# conn.net
KiCad netlist of a schematic drawn in Altium Designer
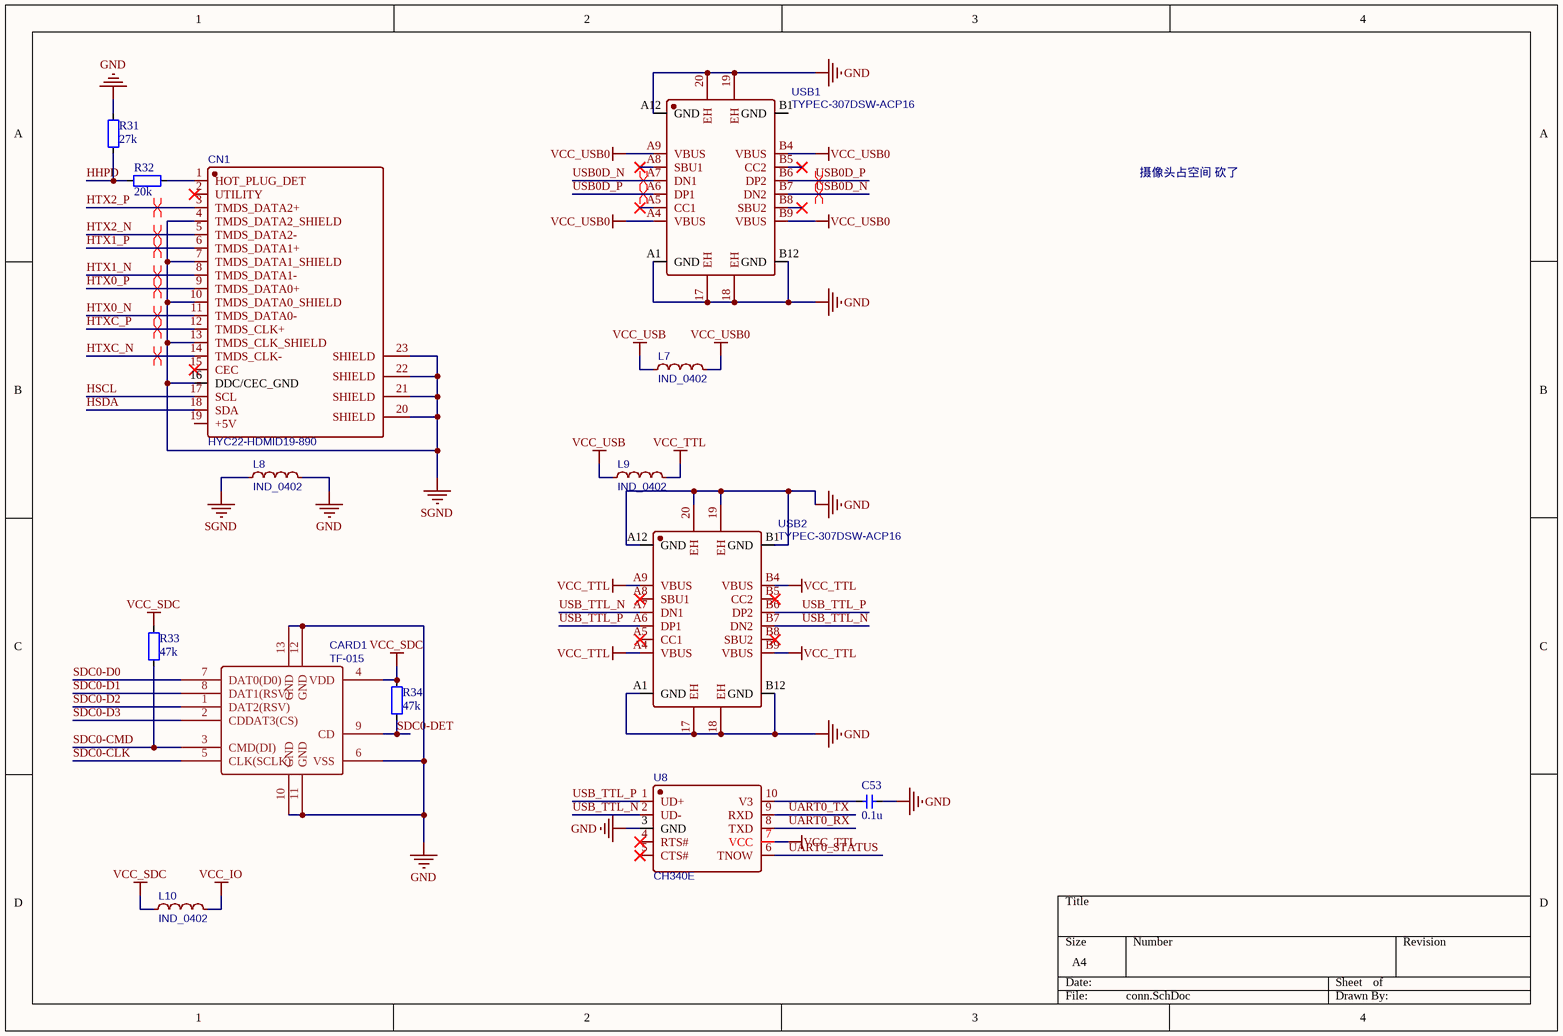
[diagram p0: conn.SchDoc]

(export (version "E")
  (design (tool "Eeschema 10.0.6"))
  (components
    (comp (ref "C53")
      (value "0.1u")
      (footprint "C0402")
      (description "Capacitor")
      (fields (field (name "Comment") "CAP-0402"))
      (libsource (lib "core") (part "CAP-0402"))
    )
    (comp (ref "CARD1")
      (value "TF-015")
      (footprint "TF-SMD_TF-015")
      (fields (field (name "BOM_SUPPLIER PART") "C113206"))
      (libsource (lib "core") (part "TF-015"))
    )
    (comp (ref "CN1")
      (value "HYC22-HDMID19-890")
      (footprint "HDMI-SMD_HYC22-HDMID19-890")
      (fields (field (name "BOM_SUPPLIER PART") "C711356") (field (name "CONTRIBUTOR") "LCSC"))
      (libsource (lib "core") (part "HYC22-HDMID19-890"))
    )
    (comp (ref "L7")
      (value "IND_0402")
      (footprint "L0402")
      (fields (field (name "CONTRIBUTOR") "LCEDA_Lib"))
      (libsource (lib "core") (part "IND_0402"))
    )
    (comp (ref "L8")
      (value "IND_0402")
      (footprint "L0402")
      (fields (field (name "CONTRIBUTOR") "LCEDA_Lib"))
      (libsource (lib "core") (part "IND_0402"))
    )
    (comp (ref "L9")
      (value "IND_0402")
      (footprint "L0402")
      (fields (field (name "CONTRIBUTOR") "LCEDA_Lib"))
      (libsource (lib "core") (part "IND_0402"))
    )
    (comp (ref "L10")
      (value "IND_0402")
      (footprint "L0402")
      (fields (field (name "CONTRIBUTOR") "LCEDA_Lib"))
      (libsource (lib "core") (part "IND_0402"))
    )
    (comp (ref "R31")
      (value "27k")
      (footprint "R0402")
      (description "Resistor")
      (fields (field (name "Comment") "RES-0402"))
      (libsource (lib "core") (part "RES-0402"))
    )
    (comp (ref "R32")
      (value "20k")
      (footprint "R0402")
      (description "Resistor")
      (fields (field (name "Comment") "RES-0402"))
      (libsource (lib "") (part "RES-0402_1"))
    )
    (comp (ref "R33")
      (value "47k")
      (footprint "R0402")
      (description "Resistor")
      (fields (field (name "Comment") "RES-0402"))
      (libsource (lib "core") (part "RES-0402"))
    )
    (comp (ref "R34")
      (value "47k")
      (footprint "R0402")
      (description "Resistor")
      (fields (field (name "Comment") "RES-0402"))
      (libsource (lib "core") (part "RES-0402"))
    )
    (comp (ref "U8")
      (value "CH340E")
      (footprint "MSOP-10_L3.0-W3.0-P0.50-LS5.0-BL")
      (fields (field (name "BOM_SUPPLIER PART") "C99652"))
      (libsource (lib "core") (part "CH340E"))
    )
    (comp (ref "USB1")
      (value "TYPEC-307DSW-ACP16")
      (footprint "USB-C-SMD_TYPEC-307DSW-ACP16")
      (fields (field (name "BOM_SUPPLIER PART") "C2840402") (field (name "CONTRIBUTOR") "LCSC"))
      (libsource (lib "core") (part "TYPEC-307DSW-ACP16"))
    )
    (comp (ref "USB2")
      (value "TYPEC-307DSW-ACP16")
      (footprint "USB-C-SMD_TYPEC-307DSW-ACP16")
      (fields (field (name "BOM_SUPPLIER PART") "C2840402") (field (name "CONTRIBUTOR") "LCSC"))
      (libsource (lib "core") (part "TYPEC-307DSW-ACP16"))
    )
  )
  (nets
    (net (code "1") (name "/HHPD") (class "Default")
      (node (ref "R31") (pin "2") (pinfunction "2_2") (pintype "passive"))
      (node (ref "R32") (pin "2") (pinfunction "2_2") (pintype "passive"))
    )
    (net (code "2") (name "/HSCL") (class "Default")
      (node (ref "CN1") (pin "17") (pinfunction "SCL_17") (pintype "passive"))
    )
    (net (code "3") (name "/HSDA") (class "Default")
      (node (ref "CN1") (pin "18") (pinfunction "SDA_18") (pintype "passive"))
    )
    (net (code "4") (name "/HTX0_N") (class "Default")
      (node (ref "CN1") (pin "11") (pinfunction "TMDS_DATA0-_11") (pintype "passive"))
    )
    (net (code "5") (name "/HTX0_P") (class "Default")
      (node (ref "CN1") (pin "9") (pinfunction "TMDS_DATA0+_9") (pintype "passive"))
    )
    (net (code "6") (name "/HTX1_N") (class "Default")
      (node (ref "CN1") (pin "8") (pinfunction "TMDS_DATA1-_8") (pintype "passive"))
    )
    (net (code "7") (name "/HTX1_P") (class "Default")
      (node (ref "CN1") (pin "6") (pinfunction "TMDS_DATA1+_6") (pintype "passive"))
    )
    (net (code "8") (name "/HTX2_N") (class "Default")
      (node (ref "CN1") (pin "5") (pinfunction "TMDS_DATA2-_5") (pintype "passive"))
    )
    (net (code "9") (name "/HTX2_P") (class "Default")
      (node (ref "CN1") (pin "3") (pinfunction "TMDS_DATA2+_3") (pintype "passive"))
    )
    (net (code "10") (name "/HTXC_N") (class "Default")
      (node (ref "CN1") (pin "14") (pinfunction "TMDS_CLK-_14") (pintype "passive"))
    )
    (net (code "11") (name "/HTXC_P") (class "Default")
      (node (ref "CN1") (pin "12") (pinfunction "TMDS_CLK+_12") (pintype "passive"))
    )
    (net (code "12") (name "/SDC0-CLK") (class "Default")
      (node (ref "CARD1") (pin "5") (pinfunction "CLK(SCLK)_5") (pintype "passive"))
    )
    (net (code "13") (name "/SDC0-CMD") (class "Default")
      (node (ref "CARD1") (pin "3") (pinfunction "CMD(DI)_3") (pintype "passive"))
      (node (ref "R33") (pin "2") (pinfunction "2_2") (pintype "passive"))
    )
    (net (code "14") (name "/SDC0-D0") (class "Default")
      (node (ref "CARD1") (pin "7") (pinfunction "DAT0(D0)_7") (pintype "passive"))
    )
    (net (code "15") (name "/SDC0-D1") (class "Default")
      (node (ref "CARD1") (pin "8") (pinfunction "DAT1(RSV)_8") (pintype "passive"))
    )
    (net (code "16") (name "/SDC0-D2") (class "Default")
      (node (ref "CARD1") (pin "1") (pinfunction "DAT2(RSV)_1") (pintype "passive"))
    )
    (net (code "17") (name "/SDC0-D3") (class "Default")
      (node (ref "CARD1") (pin "2") (pinfunction "CDDAT3(CS)_2") (pintype "passive"))
    )
    (net (code "18") (name "/SDC0-DET") (class "Default")
      (node (ref "CARD1") (pin "9") (pinfunction "CD_9") (pintype "passive"))
      (node (ref "R34") (pin "2") (pinfunction "2_2") (pintype "passive"))
    )
    (net (code "19") (name "/UART0_RX") (class "Default")
      (node (ref "U8") (pin "8") (pinfunction "TXD_8") (pintype "passive"))
    )
    (net (code "20") (name "/UART0_STATUS") (class "Default")
      (node (ref "U8") (pin "6") (pinfunction "TNOW_6") (pintype "passive"))
    )
    (net (code "21") (name "/UART0_TX") (class "Default")
      (node (ref "U8") (pin "9") (pinfunction "RXD_9") (pintype "passive"))
    )
    (net (code "22") (name "/USB0D_N") (class "Default")
      (node (ref "USB1") (pin "A7") (pinfunction "DN1_A7") (pintype "passive"))
      (node (ref "USB1") (pin "B7") (pinfunction "DN2_B7") (pintype "passive"))
    )
    (net (code "23") (name "/USB0D_P") (class "Default")
      (node (ref "USB1") (pin "A6") (pinfunction "DP1_A6") (pintype "passive"))
      (node (ref "USB1") (pin "B6") (pinfunction "DP2_B6") (pintype "passive"))
    )
    (net (code "24") (name "/USB_TTL_N") (class "Default")
      (node (ref "U8") (pin "2") (pinfunction "UD-_2") (pintype "passive"))
      (node (ref "USB2") (pin "A7") (pinfunction "DN1_A7") (pintype "passive"))
      (node (ref "USB2") (pin "B7") (pinfunction "DN2_B7") (pintype "passive"))
    )
    (net (code "25") (name "/USB_TTL_P") (class "Default")
      (node (ref "U8") (pin "1") (pinfunction "UD+_1") (pintype "passive"))
      (node (ref "USB2") (pin "A6") (pinfunction "DP1_A6") (pintype "passive"))
      (node (ref "USB2") (pin "B6") (pinfunction "DP2_B6") (pintype "passive"))
    )
    (net (code "26") (name "GND") (class "Default")
      (node (ref "C53") (pin "1") (pinfunction "1_1") (pintype "passive"))
      (node (ref "CARD1") (pin "10") (pinfunction "GND_10") (pintype "passive"))
      (node (ref "CARD1") (pin "11") (pinfunction "GND_11") (pintype "passive"))
      (node (ref "CARD1") (pin "12") (pinfunction "GND_12") (pintype "passive"))
      (node (ref "CARD1") (pin "13") (pinfunction "GND_13") (pintype "passive"))
      (node (ref "CARD1") (pin "6") (pinfunction "VSS_6") (pintype "passive"))
      (node (ref "L8") (pin "2") (pinfunction "2_2") (pintype "passive"))
      (node (ref "R31") (pin "1") (pinfunction "1_1") (pintype "passive"))
      (node (ref "U8") (pin "3") (pinfunction "GND_3") (pintype "passive"))
      (node (ref "USB1") (pin "17") (pinfunction "EH_17") (pintype "passive"))
      (node (ref "USB1") (pin "18") (pinfunction "EH_18") (pintype "passive"))
      (node (ref "USB1") (pin "19") (pinfunction "EH_19") (pintype "passive"))
      (node (ref "USB1") (pin "20") (pinfunction "EH_20") (pintype "passive"))
      (node (ref "USB1") (pin "A1") (pinfunction "GND_A1") (pintype "passive"))
      (node (ref "USB1") (pin "A12") (pinfunction "GND_A12") (pintype "passive"))
      (node (ref "USB1") (pin "B12") (pinfunction "GND_B12") (pintype "passive"))
      (node (ref "USB2") (pin "17") (pinfunction "EH_17") (pintype "passive"))
      (node (ref "USB2") (pin "18") (pinfunction "EH_18") (pintype "passive"))
      (node (ref "USB2") (pin "19") (pinfunction "EH_19") (pintype "passive"))
      (node (ref "USB2") (pin "20") (pinfunction "EH_20") (pintype "passive"))
      (node (ref "USB2") (pin "A1") (pinfunction "GND_A1") (pintype "passive"))
      (node (ref "USB2") (pin "A12") (pinfunction "GND_A12") (pintype "passive"))
      (node (ref "USB2") (pin "B1") (pinfunction "GND_B1") (pintype "passive"))
      (node (ref "USB2") (pin "B12") (pinfunction "GND_B12") (pintype "passive"))
    )
    (net (code "27") (name "Net-(CN1-HOT_PLUG_DET)") (class "Default")
      (node (ref "CN1") (pin "1") (pinfunction "HOT_PLUG_DET_1") (pintype "passive"))
      (node (ref "R32") (pin "1") (pinfunction "1_1") (pintype "passive"))
    )
    (net (code "28") (name "Net-(U8-V3)") (class "Default")
      (node (ref "C53") (pin "2") (pinfunction "2_2") (pintype "passive"))
      (node (ref "U8") (pin "10") (pinfunction "V3_10") (pintype "passive"))
    )
    (net (code "29") (name "SGND") (class "Default")
      (node (ref "CN1") (pin "10") (pinfunction "TMDS_DATA0_SHIELD_10") (pintype "passive"))
      (node (ref "CN1") (pin "13") (pinfunction "TMDS_CLK_SHIELD_13") (pintype "passive"))
      (node (ref "CN1") (pin "16") (pinfunction "DDC/CEC_GND_16") (pintype "passive"))
      (node (ref "CN1") (pin "20") (pinfunction "SHIELD_20") (pintype "passive"))
      (node (ref "CN1") (pin "21") (pinfunction "SHIELD_21") (pintype "passive"))
      (node (ref "CN1") (pin "22") (pinfunction "SHIELD_22") (pintype "passive"))
      (node (ref "CN1") (pin "23") (pinfunction "SHIELD_23") (pintype "passive"))
      (node (ref "CN1") (pin "4") (pinfunction "TMDS_DATA2_SHIELD_4") (pintype "passive"))
      (node (ref "CN1") (pin "7") (pinfunction "TMDS_DATA1_SHIELD_7") (pintype "passive"))
      (node (ref "L8") (pin "1") (pinfunction "1_1") (pintype "passive"))
    )
    (net (code "30") (name "VCC_IO") (class "Default")
      (node (ref "L10") (pin "2") (pinfunction "2_2") (pintype "passive"))
    )
    (net (code "31") (name "VCC_SDC") (class "Default")
      (node (ref "CARD1") (pin "4") (pinfunction "VDD_4") (pintype "passive"))
      (node (ref "L10") (pin "1") (pinfunction "1_1") (pintype "passive"))
      (node (ref "R33") (pin "1") (pinfunction "1_1") (pintype "passive"))
      (node (ref "R34") (pin "1") (pinfunction "1_1") (pintype "passive"))
    )
    (net (code "32") (name "VCC_TTL") (class "Default")
      (node (ref "L9") (pin "2") (pinfunction "2_2") (pintype "passive"))
      (node (ref "U8") (pin "7") (pinfunction "VCC_7") (pintype "passive"))
      (node (ref "USB2") (pin "A4") (pinfunction "VBUS_A4") (pintype "passive"))
      (node (ref "USB2") (pin "A9") (pinfunction "VBUS_A9") (pintype "passive"))
      (node (ref "USB2") (pin "B4") (pinfunction "VBUS_B4") (pintype "passive"))
      (node (ref "USB2") (pin "B9") (pinfunction "VBUS_B9") (pintype "passive"))
    )
    (net (code "33") (name "VCC_USB") (class "Default")
      (node (ref "L7") (pin "1") (pinfunction "1_1") (pintype "passive"))
      (node (ref "L9") (pin "1") (pinfunction "1_1") (pintype "passive"))
    )
    (net (code "34") (name "VCC_USB0") (class "Default")
      (node (ref "L7") (pin "2") (pinfunction "2_2") (pintype "passive"))
      (node (ref "USB1") (pin "A4") (pinfunction "VBUS_A4") (pintype "passive"))
      (node (ref "USB1") (pin "A9") (pinfunction "VBUS_A9") (pintype "passive"))
      (node (ref "USB1") (pin "B4") (pinfunction "VBUS_B4") (pintype "passive"))
      (node (ref "USB1") (pin "B9") (pinfunction "VBUS_B9") (pintype "passive"))
    )
    (net (code "35") (name "unconnected-(CN1-+5V-Pad19)") (class "Default")
      (node (ref "CN1") (pin "19") (pinfunction "+5V_19") (pintype "passive"))
    )
    (net (code "36") (name "unconnected-(CN1-CEC-Pad15)") (class "Default")
      (node (ref "CN1") (pin "15") (pinfunction "CEC_15") (pintype "passive+no_connect"))
    )
    (net (code "37") (name "unconnected-(CN1-UTILITY-Pad2)") (class "Default")
      (node (ref "CN1") (pin "2") (pinfunction "UTILITY_2") (pintype "passive+no_connect"))
    )
    (net (code "38") (name "unconnected-(U8-CTS#-Pad5)") (class "Default")
      (node (ref "U8") (pin "5") (pinfunction "CTS#_5") (pintype "passive+no_connect"))
    )
    (net (code "39") (name "unconnected-(U8-RTS#-Pad4)") (class "Default")
      (node (ref "U8") (pin "4") (pinfunction "RTS#_4") (pintype "passive+no_connect"))
    )
    (net (code "40") (name "unconnected-(USB1-CC1-PadA5)") (class "Default")
      (node (ref "USB1") (pin "A5") (pinfunction "CC1_A5") (pintype "passive+no_connect"))
    )
    (net (code "41") (name "unconnected-(USB1-CC2-PadB5)") (class "Default")
      (node (ref "USB1") (pin "B5") (pinfunction "CC2_B5") (pintype "passive+no_connect"))
    )
    (net (code "42") (name "unconnected-(USB1-GND-PadB1)") (class "Default")
      (node (ref "USB1") (pin "B1") (pinfunction "GND_B1") (pintype "passive"))
    )
    (net (code "43") (name "unconnected-(USB1-SBU1-PadA8)") (class "Default")
      (node (ref "USB1") (pin "A8") (pinfunction "SBU1_A8") (pintype "passive+no_connect"))
    )
    (net (code "44") (name "unconnected-(USB1-SBU2-PadB8)") (class "Default")
      (node (ref "USB1") (pin "B8") (pinfunction "SBU2_B8") (pintype "passive+no_connect"))
    )
    (net (code "45") (name "unconnected-(USB2-CC1-PadA5)") (class "Default")
      (node (ref "USB2") (pin "A5") (pinfunction "CC1_A5") (pintype "passive+no_connect"))
    )
    (net (code "46") (name "unconnected-(USB2-CC2-PadB5)") (class "Default")
      (node (ref "USB2") (pin "B5") (pinfunction "CC2_B5") (pintype "passive+no_connect"))
    )
    (net (code "47") (name "unconnected-(USB2-SBU1-PadA8)") (class "Default")
      (node (ref "USB2") (pin "A8") (pinfunction "SBU1_A8") (pintype "passive+no_connect"))
    )
    (net (code "48") (name "unconnected-(USB2-SBU2-PadB8)") (class "Default")
      (node (ref "USB2") (pin "B8") (pinfunction "SBU2_B8") (pintype "passive+no_connect"))
    )
  )
)
